# POE_Injector.net
KiCad netlist of a schematic drawn in EAGLE
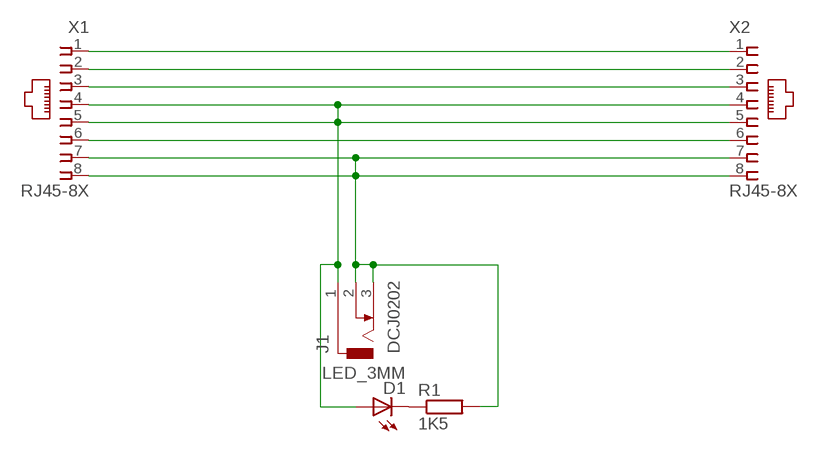
[diagram p0: schematic, sheet 1]

(export (version "E")
  (design (tool "Eeschema 10.0.6"))
  (components
    (comp (ref "D1")
      (value "LED_3MM")
      (footprint "eagle-import:LED3MM")
      (libsource (lib "eagle-import") (part "LED_3MM"))
    )
    (comp (ref "J1")
      (value "DCJ0202")
      (footprint "eagle-import:DCJ0202")
      (libsource (lib "eagle-import") (part "DCJ0202"))
    )
    (comp (ref "R1")
      (value "1K5")
      (footprint "eagle-import:R1206")
      (libsource (lib "eagle-import") (part "R_1206"))
    )
    (comp (ref "X1")
      (value "RJ45-8X")
      (footprint "eagle-import:RJ45-NO-SHIELD")
      (libsource (lib "eagle-import") (part "RJ45-8X"))
    )
    (comp (ref "X2")
      (value "RJ45-8X")
      (footprint "eagle-import:RJ45-NO-SHIELD")
      (libsource (lib "eagle-import") (part "RJ45-8X"))
    )
  )
  (nets
    (net (code "1") (name "Net-(D1-C)") (class "Default")
      (node (ref "D1") (pin "K") (pinfunction "C_K") (pintype "passive"))
      (node (ref "R1") (pin "1") (pinfunction "1_1") (pintype "passive"))
    )
    (net (code "2") (name "Net-(D1-PadA)") (class "Default")
      (node (ref "D1") (pin "A") (pinfunction "A_A") (pintype "passive"))
      (node (ref "J1") (pin "1") (pinfunction "1_1") (pintype "passive"))
      (node (ref "X1") (pin "4") (pinfunction "4_4") (pintype "passive"))
      (node (ref "X1") (pin "5") (pinfunction "5_5") (pintype "passive"))
      (node (ref "X2") (pin "4") (pinfunction "4_4") (pintype "passive"))
      (node (ref "X2") (pin "5") (pinfunction "5_5") (pintype "passive"))
    )
    (net (code "3") (name "Net-(J1-Pad2)") (class "Default")
      (node (ref "J1") (pin "2") (pinfunction "2_2") (pintype "passive"))
      (node (ref "J1") (pin "3") (pinfunction "3_3") (pintype "passive"))
      (node (ref "R1") (pin "2") (pinfunction "2_2") (pintype "passive"))
      (node (ref "X1") (pin "7") (pinfunction "7_7") (pintype "passive"))
      (node (ref "X1") (pin "8") (pinfunction "8_8") (pintype "passive"))
      (node (ref "X2") (pin "7") (pinfunction "7_7") (pintype "passive"))
      (node (ref "X2") (pin "8") (pinfunction "8_8") (pintype "passive"))
    )
    (net (code "4") (name "Net-(X1-Pad1)") (class "Default")
      (node (ref "X1") (pin "1") (pinfunction "1_1") (pintype "passive"))
      (node (ref "X2") (pin "1") (pinfunction "1_1") (pintype "passive"))
    )
    (net (code "5") (name "Net-(X1-Pad2)") (class "Default")
      (node (ref "X1") (pin "2") (pinfunction "2_2") (pintype "passive"))
      (node (ref "X2") (pin "2") (pinfunction "2_2") (pintype "passive"))
    )
    (net (code "6") (name "Net-(X1-Pad3)") (class "Default")
      (node (ref "X1") (pin "3") (pinfunction "3_3") (pintype "passive"))
      (node (ref "X2") (pin "3") (pinfunction "3_3") (pintype "passive"))
    )
    (net (code "7") (name "Net-(X1-Pad6)") (class "Default")
      (node (ref "X1") (pin "6") (pinfunction "6_6") (pintype "passive"))
      (node (ref "X2") (pin "6") (pinfunction "6_6") (pintype "passive"))
    )
  )
)
